# Standby_Power.net
KiCad netlist of a schematic drawn in EAGLE
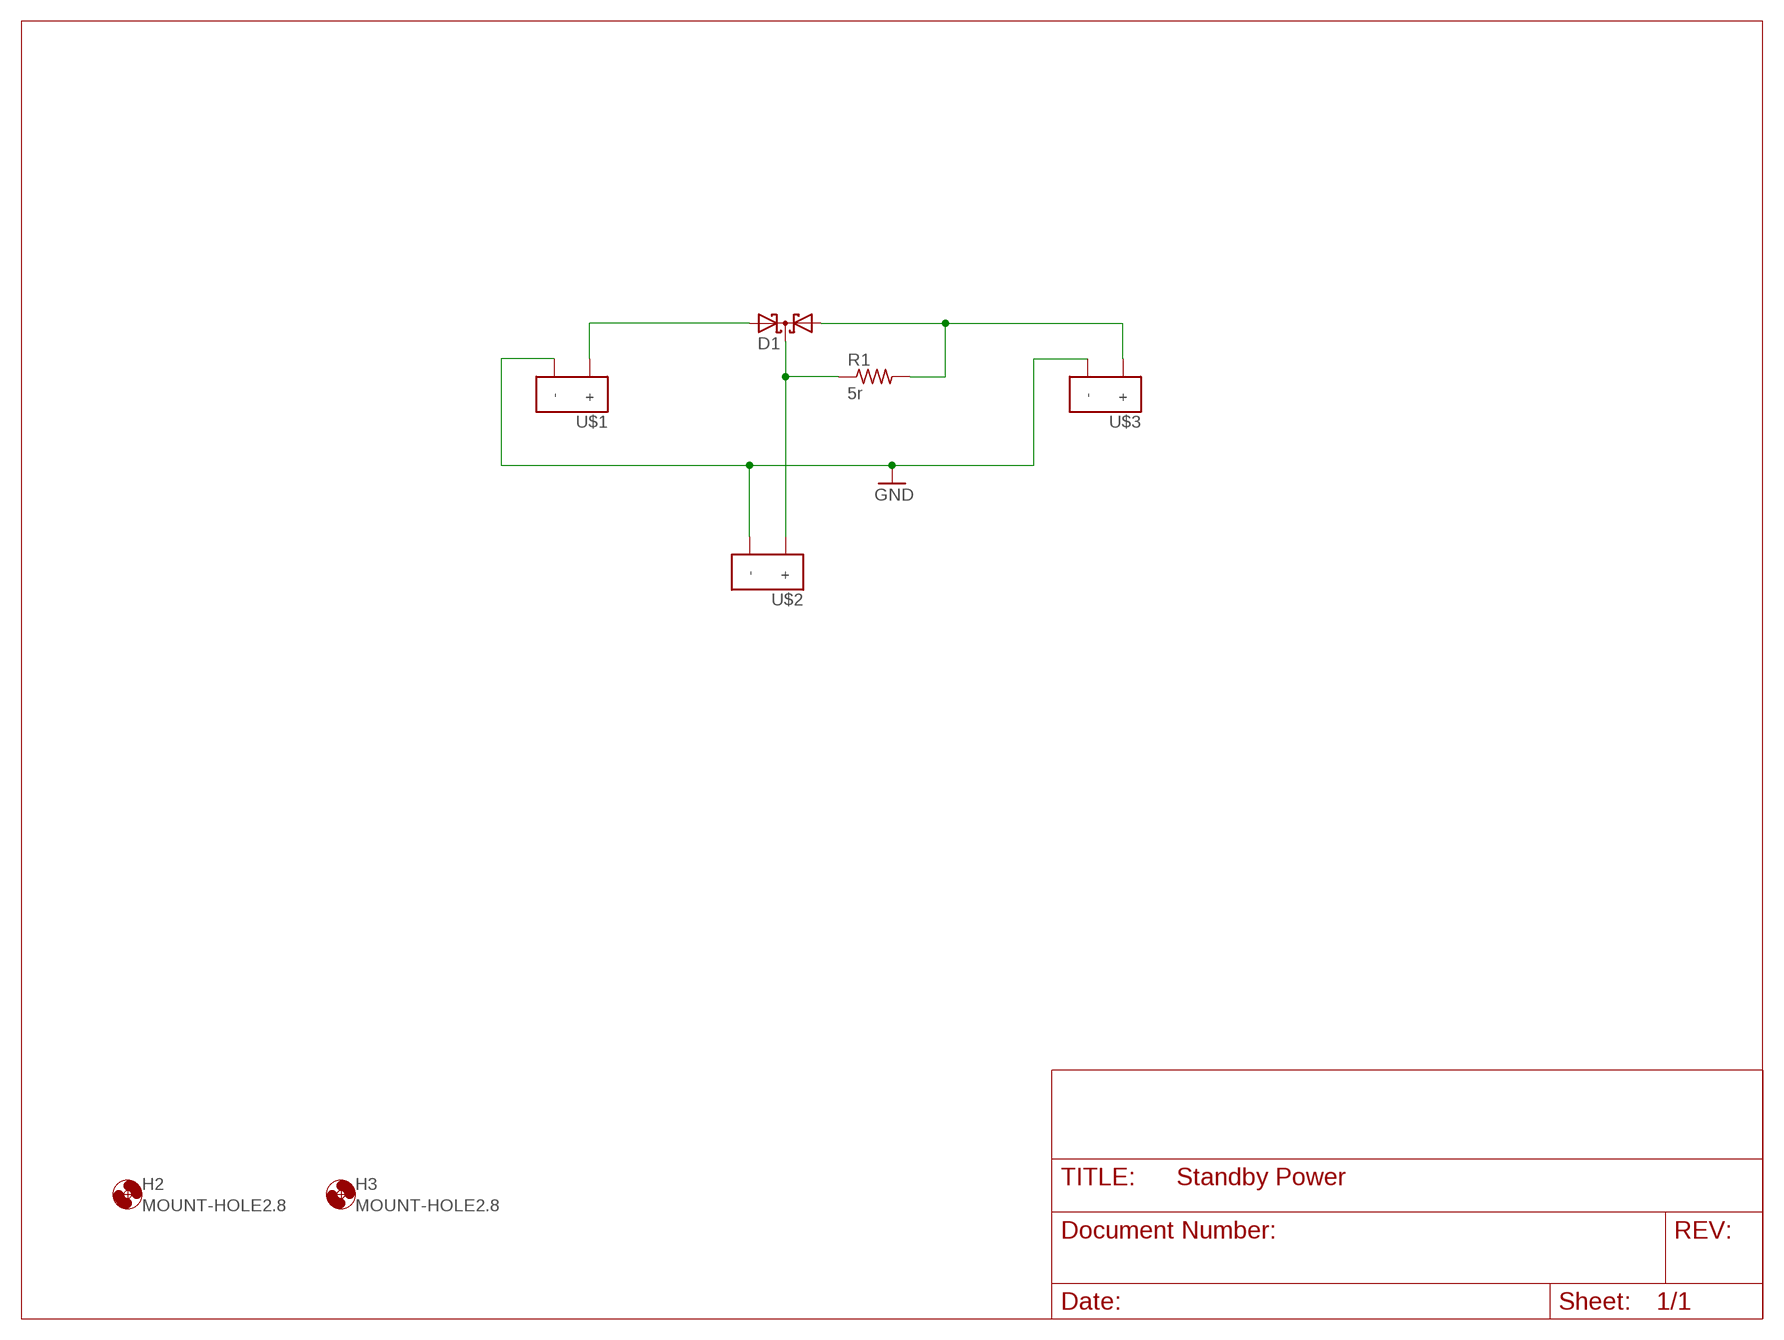
[diagram p0: schematic, sheet 1]

(export (version "E")
  (design (tool "Eeschema 10.0.6"))
  (components
    (comp (ref "D1")
      (value "DIODE_2SCHOTTKY-SOT82H")
      (footprint "eagle-import:SOT82L")
      (libsource (lib "eagle-import") (part "DIODE_2SCHOTTKY-SOT82H"))
    )
    (comp (ref "H2")
      (value "MOUNT-HOLE2.8")
      (footprint "eagle-import:2,8")
      (libsource (lib "eagle-import") (part "MOUNT-HOLE2.8"))
    )
    (comp (ref "H3")
      (value "MOUNT-HOLE2.8")
      (footprint "eagle-import:2,8")
      (libsource (lib "eagle-import") (part "MOUNT-HOLE2.8"))
    )
    (comp (ref "R1")
      (value "5r")
      (footprint "eagle-import:V235_17")
      (libsource (lib "eagle-import") (part "R-US_V235/17"))
    )
    (comp (ref "U$1")
      (value "POWERPOLE-HORZ-NARROW-CONTACT")
      (footprint "eagle-import:HORZ-NARROW-CONTACT")
      (libsource (lib "eagle-import") (part "POWERPOLE-HORZ-NARROW-CONTACT"))
    )
    (comp (ref "U$2")
      (value "POWERPOLE-HORZ-NARROW-CONTACT")
      (footprint "eagle-import:HORZ-NARROW-CONTACT")
      (libsource (lib "eagle-import") (part "POWERPOLE-HORZ-NARROW-CONTACT"))
    )
    (comp (ref "U$3")
      (value "POWERPOLE-HORZ-NARROW-CONTACT")
      (footprint "eagle-import:HORZ-NARROW-CONTACT")
      (libsource (lib "eagle-import") (part "POWERPOLE-HORZ-NARROW-CONTACT"))
    )
  )
  (nets
    (net (code "1") (name "GND") (class "Default")
      (node (ref "U$1") (pin "-") (pinfunction "-_-") (pintype "bidirectional"))
      (node (ref "U$2") (pin "-") (pinfunction "-_-") (pintype "bidirectional"))
      (node (ref "U$3") (pin "-") (pinfunction "-_-") (pintype "bidirectional"))
    )
    (net (code "2") (name "Net-(D1-PadA1)") (class "Default")
      (node (ref "D1") (pin "A1") (pinfunction "A1_A1") (pintype "passive"))
      (node (ref "R1") (pin "2") (pinfunction "2_2") (pintype "passive"))
      (node (ref "U$3") (pin "+") (pinfunction "+_+") (pintype "bidirectional"))
    )
    (net (code "3") (name "Net-(D1-PadA2)") (class "Default")
      (node (ref "D1") (pin "A2") (pinfunction "A2_A2") (pintype "passive"))
      (node (ref "U$1") (pin "+") (pinfunction "+_+") (pintype "bidirectional"))
    )
    (net (code "4") (name "Net-(D1-PadC)") (class "Default")
      (node (ref "D1") (pin "C") (pinfunction "C_C") (pintype "passive"))
      (node (ref "R1") (pin "1") (pinfunction "1_1") (pintype "passive"))
      (node (ref "U$2") (pin "+") (pinfunction "+_+") (pintype "bidirectional"))
    )
  )
)
